# LED_Light_Bulb.net
KiCad netlist of a schematic drawn in EAGLE
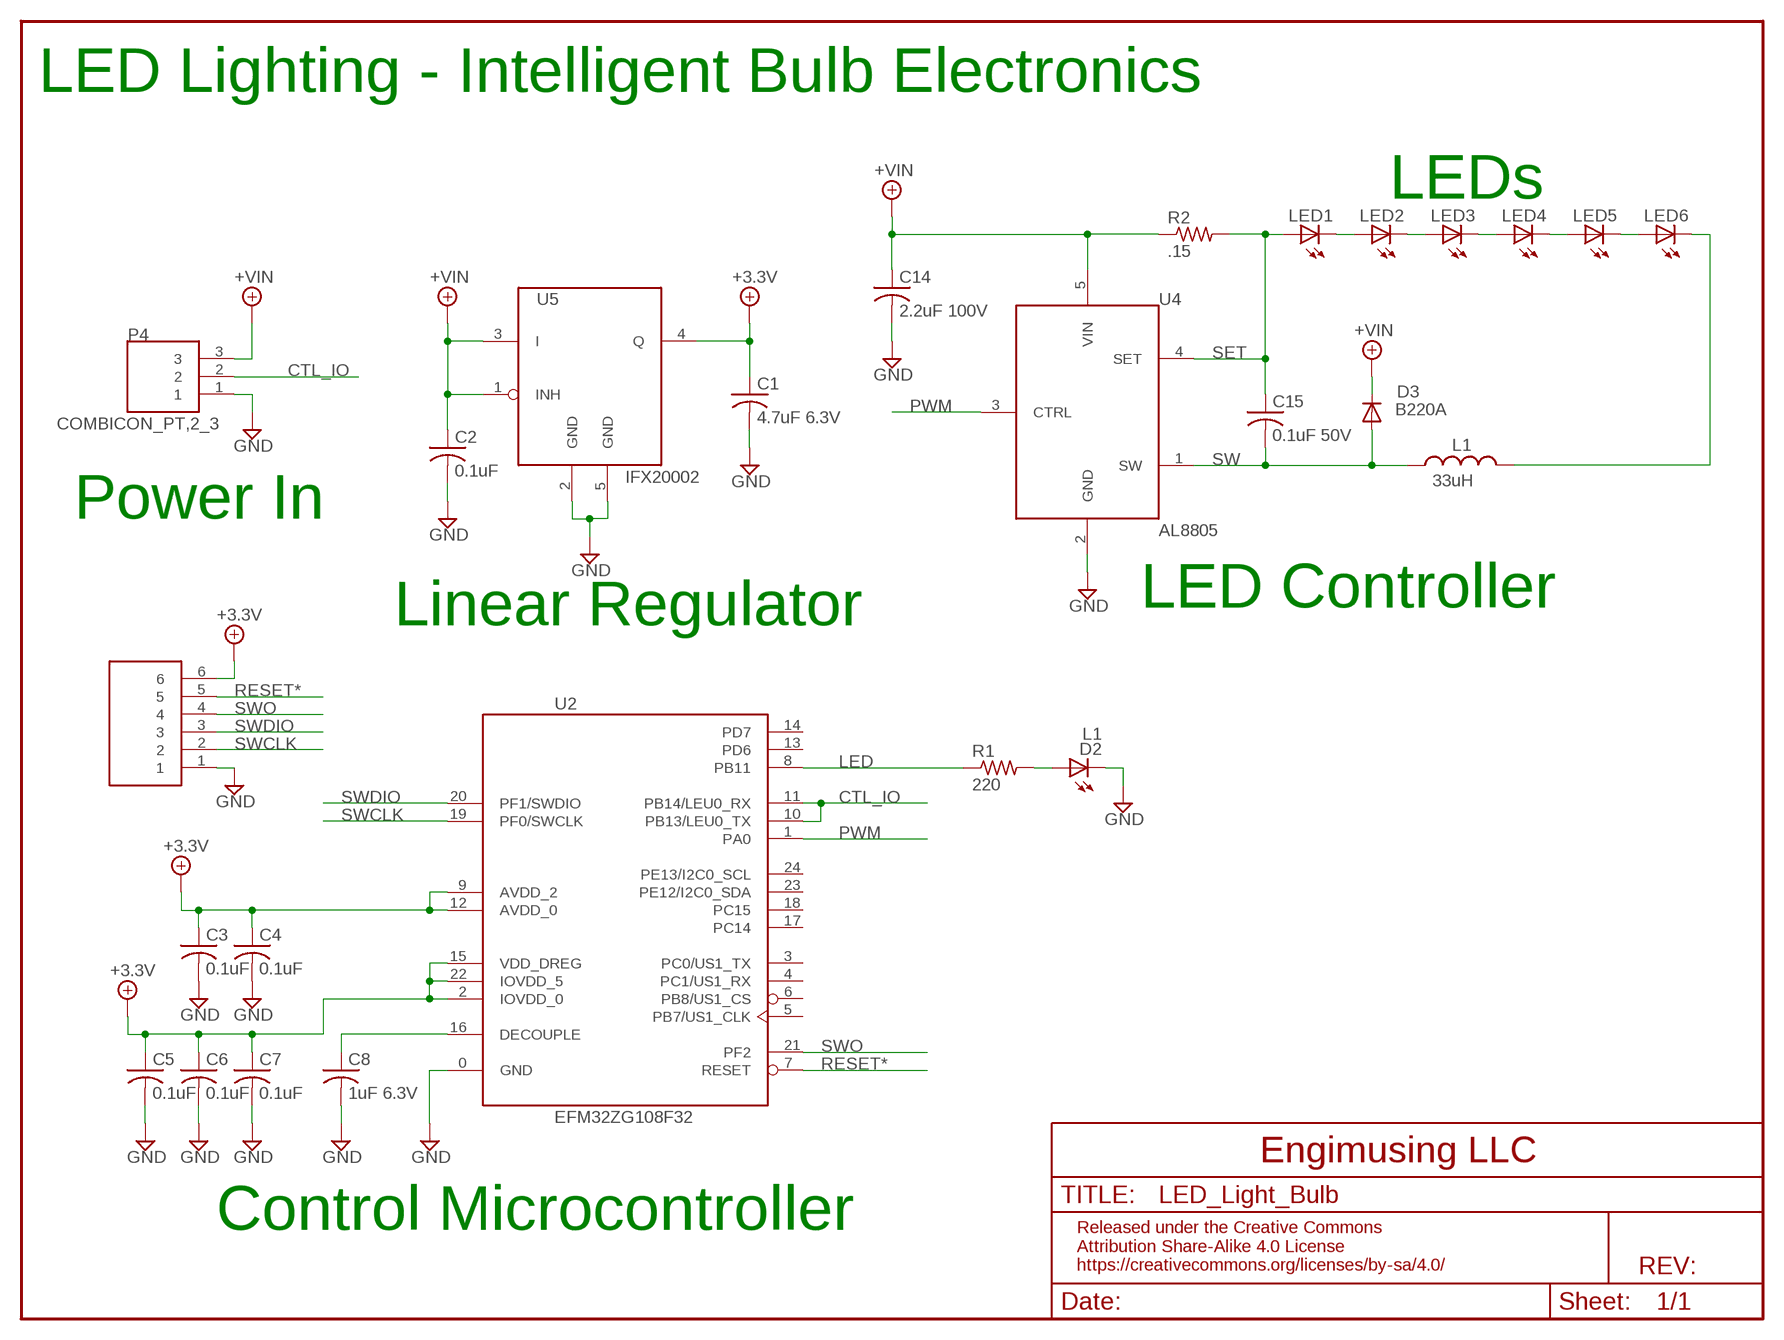
[diagram p0: schematic, sheet 1]

(export (version "E")
  (design (tool "Eeschema 10.0.6"))
  (components
    (comp (ref "C1")
      (value "4.7uF 6.3V")
      (footprint "eagle-import:C0603")
      (libsource (lib "eagle-import") (part "C-USC0603"))
    )
    (comp (ref "C2")
      (value "0.1uF")
      (footprint "eagle-import:C0603")
      (libsource (lib "eagle-import") (part "C-USC0603"))
    )
    (comp (ref "C3")
      (value "0.1uF")
      (footprint "eagle-import:C0603")
      (libsource (lib "eagle-import") (part "C-USC0603"))
    )
    (comp (ref "C4")
      (value "0.1uF")
      (footprint "eagle-import:C0603")
      (libsource (lib "eagle-import") (part "C-USC0603"))
    )
    (comp (ref "C5")
      (value "0.1uF")
      (footprint "eagle-import:C0603")
      (libsource (lib "eagle-import") (part "C-USC0603"))
    )
    (comp (ref "C6")
      (value "0.1uF")
      (footprint "eagle-import:C0603")
      (libsource (lib "eagle-import") (part "C-USC0603"))
    )
    (comp (ref "C7")
      (value "0.1uF")
      (footprint "eagle-import:C0603")
      (libsource (lib "eagle-import") (part "C-USC0603"))
    )
    (comp (ref "C8")
      (value "1uF 6.3V")
      (footprint "eagle-import:C0603")
      (libsource (lib "eagle-import") (part "C-USC0603"))
    )
    (comp (ref "C14")
      (value "2.2uF 100V")
      (footprint "eagle-import:C1210K")
      (libsource (lib "eagle-import") (part "C-USC1210K"))
    )
    (comp (ref "C15")
      (value "0.1uF 50V")
      (footprint "eagle-import:C0805")
      (libsource (lib "eagle-import") (part "C-USC0805"))
    )
    (comp (ref "D2")
      (value "L1")
      (footprint "eagle-import:CHIP-LED0603")
      (libsource (lib "eagle-import") (part "led_LEDCHIP-LED0603"))
    )
    (comp (ref "D3")
      (value "B220A")
      (footprint "eagle-import:DO214SMA")
      (libsource (lib "eagle-import") (part "DIODE"))
    )
    (comp (ref "L1")
      (value "33uH")
      (footprint "eagle-import:SRN6045")
      (libsource (lib "eagle-import") (part "INDUCTOR"))
    )
    (comp (ref "LED1")
      (value "LED-MX3")
      (footprint "eagle-import:LED_5X5")
      (libsource (lib "eagle-import") (part "LED-MX3"))
    )
    (comp (ref "LED2")
      (value "LED-MX3")
      (footprint "eagle-import:LED_5X5")
      (libsource (lib "eagle-import") (part "LED-MX3"))
    )
    (comp (ref "LED3")
      (value "LED-MX3")
      (footprint "eagle-import:LED_5X5")
      (libsource (lib "eagle-import") (part "LED-MX3"))
    )
    (comp (ref "LED4")
      (value "LED-MX3")
      (footprint "eagle-import:LED_5X5")
      (libsource (lib "eagle-import") (part "LED-MX3"))
    )
    (comp (ref "LED5")
      (value "LED-MX3")
      (footprint "eagle-import:LED_5X5")
      (libsource (lib "eagle-import") (part "LED-MX3"))
    )
    (comp (ref "LED6")
      (value "LED-MX3")
      (footprint "eagle-import:LED_5X5")
      (libsource (lib "eagle-import") (part "LED-MX3"))
    )
    (comp (ref "P3")
      (value "DF11-6_STRAIGHT_PIN")
      (footprint "eagle-import:DF11SP-6-H")
      (libsource (lib "eagle-import") (part "DF11-6_STRAIGHT_PIN"))
    )
    (comp (ref "P4")
      (value "COMBICON_PT,2_3")
      (footprint "eagle-import:PT_2,5_3-5,0-H")
      (libsource (lib "eagle-import") (part "COMBICON_PT,2_3"))
    )
    (comp (ref "R1")
      (value "220")
      (footprint "eagle-import:R0603")
      (libsource (lib "eagle-import") (part "R-USR0603"))
    )
    (comp (ref "R2")
      (value ".15")
      (footprint "eagle-import:R0805")
      (libsource (lib "eagle-import") (part "R-USR0805"))
    )
    (comp (ref "U2")
      (value "EFM32ZG108F32")
      (footprint "eagle-import:QFN24_5X5")
      (libsource (lib "eagle-import") (part "EFM32ZG108F32"))
    )
    (comp (ref "U4")
      (value "AL8805")
      (footprint "eagle-import:SOT-23-5A")
      (libsource (lib "eagle-import") (part "AL8805"))
    )
    (comp (ref "U5")
      (value "IFX20002")
      (footprint "eagle-import:PG-SCT595-5")
      (libsource (lib "eagle-import") (part "IFX20002"))
    )
  )
  (nets
    (net (code "1") (name "+3.3V") (class "Default")
      (node (ref "C1") (pin "1") (pinfunction "1_1") (pintype "passive"))
      (node (ref "C3") (pin "1") (pinfunction "1_1") (pintype "passive"))
      (node (ref "C4") (pin "1") (pinfunction "1_1") (pintype "passive"))
      (node (ref "C5") (pin "1") (pinfunction "1_1") (pintype "passive"))
      (node (ref "C6") (pin "1") (pinfunction "1_1") (pintype "passive"))
      (node (ref "C7") (pin "1") (pinfunction "1_1") (pintype "passive"))
      (node (ref "P3") (pin "6") (pinfunction "6_6") (pintype "passive"))
      (node (ref "U2") (pin "12") (pinfunction "AVDD_0_12") (pintype "power_in"))
      (node (ref "U2") (pin "15") (pinfunction "VDD_DREG_15") (pintype "power_in"))
      (node (ref "U2") (pin "2") (pinfunction "IOVDD_0_2") (pintype "power_in"))
      (node (ref "U2") (pin "22") (pinfunction "IOVDD_5_22") (pintype "power_in"))
      (node (ref "U2") (pin "9") (pinfunction "AVDD_2_9") (pintype "power_in"))
      (node (ref "U5") (pin "4") (pinfunction "Q_4") (pintype "power_in"))
    )
    (net (code "2") (name "+VIN") (class "Default")
      (node (ref "C14") (pin "1") (pinfunction "1_1") (pintype "passive"))
      (node (ref "C2") (pin "1") (pinfunction "1_1") (pintype "passive"))
      (node (ref "D3") (pin "1") (pinfunction "C_1") (pintype "passive"))
      (node (ref "P4") (pin "3") (pinfunction "3_3") (pintype "passive"))
      (node (ref "R2") (pin "1") (pinfunction "1_1") (pintype "passive"))
      (node (ref "U4") (pin "5") (pinfunction "VIN_5") (pintype "bidirectional"))
      (node (ref "U5") (pin "1") (pinfunction "INH_1") (pintype "input"))
      (node (ref "U5") (pin "3") (pinfunction "I_3") (pintype "power_in"))
    )
    (net (code "3") (name "/CTL_IO") (class "Default")
      (node (ref "P4") (pin "2") (pinfunction "2_2") (pintype "passive"))
      (node (ref "U2") (pin "10") (pinfunction "PB13/LEU0_TX_10") (pintype "bidirectional"))
      (node (ref "U2") (pin "11") (pinfunction "PB14/LEU0_RX_11") (pintype "bidirectional"))
    )
    (net (code "4") (name "/LED") (class "Default")
      (node (ref "R1") (pin "1") (pinfunction "1_1") (pintype "passive"))
      (node (ref "U2") (pin "8") (pinfunction "PB11_8") (pintype "bidirectional"))
    )
    (net (code "5") (name "/PWM") (class "Default")
      (node (ref "U2") (pin "1") (pinfunction "PA0_1") (pintype "bidirectional"))
      (node (ref "U4") (pin "3") (pinfunction "CTRL_3") (pintype "bidirectional"))
    )
    (net (code "6") (name "/RESET*") (class "Default")
      (node (ref "P3") (pin "5") (pinfunction "5_5") (pintype "passive"))
      (node (ref "U2") (pin "7") (pinfunction "RESET_7") (pintype "input"))
    )
    (net (code "7") (name "/SET") (class "Default")
      (node (ref "C15") (pin "1") (pinfunction "1_1") (pintype "passive"))
      (node (ref "LED1") (pin "A") (pinfunction "A_A") (pintype "passive"))
      (node (ref "R2") (pin "2") (pinfunction "2_2") (pintype "passive"))
      (node (ref "U4") (pin "4") (pinfunction "SET_4") (pintype "bidirectional"))
    )
    (net (code "8") (name "/SW") (class "Default")
      (node (ref "C15") (pin "2") (pinfunction "2_2") (pintype "passive"))
      (node (ref "D3") (pin "2") (pinfunction "A_2") (pintype "passive"))
      (node (ref "L1") (pin "1") (pinfunction "1_1") (pintype "passive"))
      (node (ref "U4") (pin "1") (pinfunction "SW_1") (pintype "bidirectional"))
    )
    (net (code "9") (name "/SWCLK") (class "Default")
      (node (ref "P3") (pin "2") (pinfunction "2_2") (pintype "passive"))
      (node (ref "U2") (pin "19") (pinfunction "PF0/SWCLK_19") (pintype "bidirectional"))
    )
    (net (code "10") (name "/SWDIO") (class "Default")
      (node (ref "P3") (pin "3") (pinfunction "3_3") (pintype "passive"))
      (node (ref "U2") (pin "20") (pinfunction "PF1/SWDIO_20") (pintype "bidirectional"))
    )
    (net (code "11") (name "/SWO") (class "Default")
      (node (ref "P3") (pin "4") (pinfunction "4_4") (pintype "passive"))
      (node (ref "U2") (pin "21") (pinfunction "PF2_21") (pintype "bidirectional"))
    )
    (net (code "12") (name "GND") (class "Default")
      (node (ref "C1") (pin "2") (pinfunction "2_2") (pintype "passive"))
      (node (ref "C14") (pin "2") (pinfunction "2_2") (pintype "passive"))
      (node (ref "C2") (pin "2") (pinfunction "2_2") (pintype "passive"))
      (node (ref "C3") (pin "2") (pinfunction "2_2") (pintype "passive"))
      (node (ref "C4") (pin "2") (pinfunction "2_2") (pintype "passive"))
      (node (ref "C5") (pin "2") (pinfunction "2_2") (pintype "passive"))
      (node (ref "C6") (pin "2") (pinfunction "2_2") (pintype "passive"))
      (node (ref "C7") (pin "2") (pinfunction "2_2") (pintype "passive"))
      (node (ref "C8") (pin "2") (pinfunction "2_2") (pintype "passive"))
      (node (ref "D2") (pin "C") (pinfunction "C_C") (pintype "passive"))
      (node (ref "P3") (pin "1") (pinfunction "1_1") (pintype "passive"))
      (node (ref "P4") (pin "1") (pinfunction "1_1") (pintype "passive"))
      (node (ref "U2") (pin "0") (pinfunction "GND_0") (pintype "power_in"))
      (node (ref "U4") (pin "2") (pinfunction "GND_2") (pintype "bidirectional"))
      (node (ref "U5") (pin "2") (pinfunction "GND_2") (pintype "bidirectional"))
      (node (ref "U5") (pin "5") (pinfunction "GND_5") (pintype "bidirectional"))
    )
    (net (code "13") (name "Net-(D2-PadA)") (class "Default")
      (node (ref "D2") (pin "A") (pinfunction "A_A") (pintype "passive"))
      (node (ref "R1") (pin "2") (pinfunction "2_2") (pintype "passive"))
    )
    (net (code "14") (name "Net-(L1-Pad2)") (class "Default")
      (node (ref "L1") (pin "2") (pinfunction "2_2") (pintype "passive"))
      (node (ref "LED6") (pin "C") (pinfunction "C_C") (pintype "passive"))
    )
    (net (code "15") (name "Net-(LED1-PadC)") (class "Default")
      (node (ref "LED1") (pin "C") (pinfunction "C_C") (pintype "passive"))
      (node (ref "LED2") (pin "A") (pinfunction "A_A") (pintype "passive"))
    )
    (net (code "16") (name "Net-(LED2-PadC)") (class "Default")
      (node (ref "LED2") (pin "C") (pinfunction "C_C") (pintype "passive"))
      (node (ref "LED3") (pin "A") (pinfunction "A_A") (pintype "passive"))
    )
    (net (code "17") (name "Net-(LED3-PadC)") (class "Default")
      (node (ref "LED3") (pin "C") (pinfunction "C_C") (pintype "passive"))
      (node (ref "LED4") (pin "A") (pinfunction "A_A") (pintype "passive"))
    )
    (net (code "18") (name "Net-(LED4-PadC)") (class "Default")
      (node (ref "LED4") (pin "C") (pinfunction "C_C") (pintype "passive"))
      (node (ref "LED5") (pin "A") (pinfunction "A_A") (pintype "passive"))
    )
    (net (code "19") (name "Net-(LED5-PadC)") (class "Default")
      (node (ref "LED5") (pin "C") (pinfunction "C_C") (pintype "passive"))
      (node (ref "LED6") (pin "A") (pinfunction "A_A") (pintype "passive"))
    )
    (net (code "20") (name "Net-(U2-DECOUPLE)") (class "Default")
      (node (ref "C8") (pin "1") (pinfunction "1_1") (pintype "passive"))
      (node (ref "U2") (pin "16") (pinfunction "DECOUPLE_16") (pintype "passive"))
    )
    (net (code "21") (name "unconnected-(U2-PB7{slash}US1_CLK-Pad5)") (class "Default")
      (node (ref "U2") (pin "5") (pinfunction "PB7/US1_CLK_5") (pintype "bidirectional"))
    )
    (net (code "22") (name "unconnected-(U2-PB8{slash}US1_CS-Pad6)") (class "Default")
      (node (ref "U2") (pin "6") (pinfunction "PB8/US1_CS_6") (pintype "bidirectional"))
    )
    (net (code "23") (name "unconnected-(U2-PC0{slash}US1_TX-Pad3)") (class "Default")
      (node (ref "U2") (pin "3") (pinfunction "PC0/US1_TX_3") (pintype "bidirectional"))
    )
    (net (code "24") (name "unconnected-(U2-PC1{slash}US1_RX-Pad4)") (class "Default")
      (node (ref "U2") (pin "4") (pinfunction "PC1/US1_RX_4") (pintype "bidirectional"))
    )
    (net (code "25") (name "unconnected-(U2-PC14-Pad17)") (class "Default")
      (node (ref "U2") (pin "17") (pinfunction "PC14_17") (pintype "bidirectional"))
    )
    (net (code "26") (name "unconnected-(U2-PC15-Pad18)") (class "Default")
      (node (ref "U2") (pin "18") (pinfunction "PC15_18") (pintype "bidirectional"))
    )
    (net (code "27") (name "unconnected-(U2-PD6-Pad13)") (class "Default")
      (node (ref "U2") (pin "13") (pinfunction "PD6_13") (pintype "bidirectional"))
    )
    (net (code "28") (name "unconnected-(U2-PD7-Pad14)") (class "Default")
      (node (ref "U2") (pin "14") (pinfunction "PD7_14") (pintype "bidirectional"))
    )
    (net (code "29") (name "unconnected-(U2-PE12{slash}I2C0_SDA-Pad23)") (class "Default")
      (node (ref "U2") (pin "23") (pinfunction "PE12/I2C0_SDA_23") (pintype "bidirectional"))
    )
    (net (code "30") (name "unconnected-(U2-PE13{slash}I2C0_SCL-Pad24)") (class "Default")
      (node (ref "U2") (pin "24") (pinfunction "PE13/I2C0_SCL_24") (pintype "bidirectional"))
    )
  )
)
